# nano_control_station.net
KiCad netlist of a schematic drawn in EAGLE
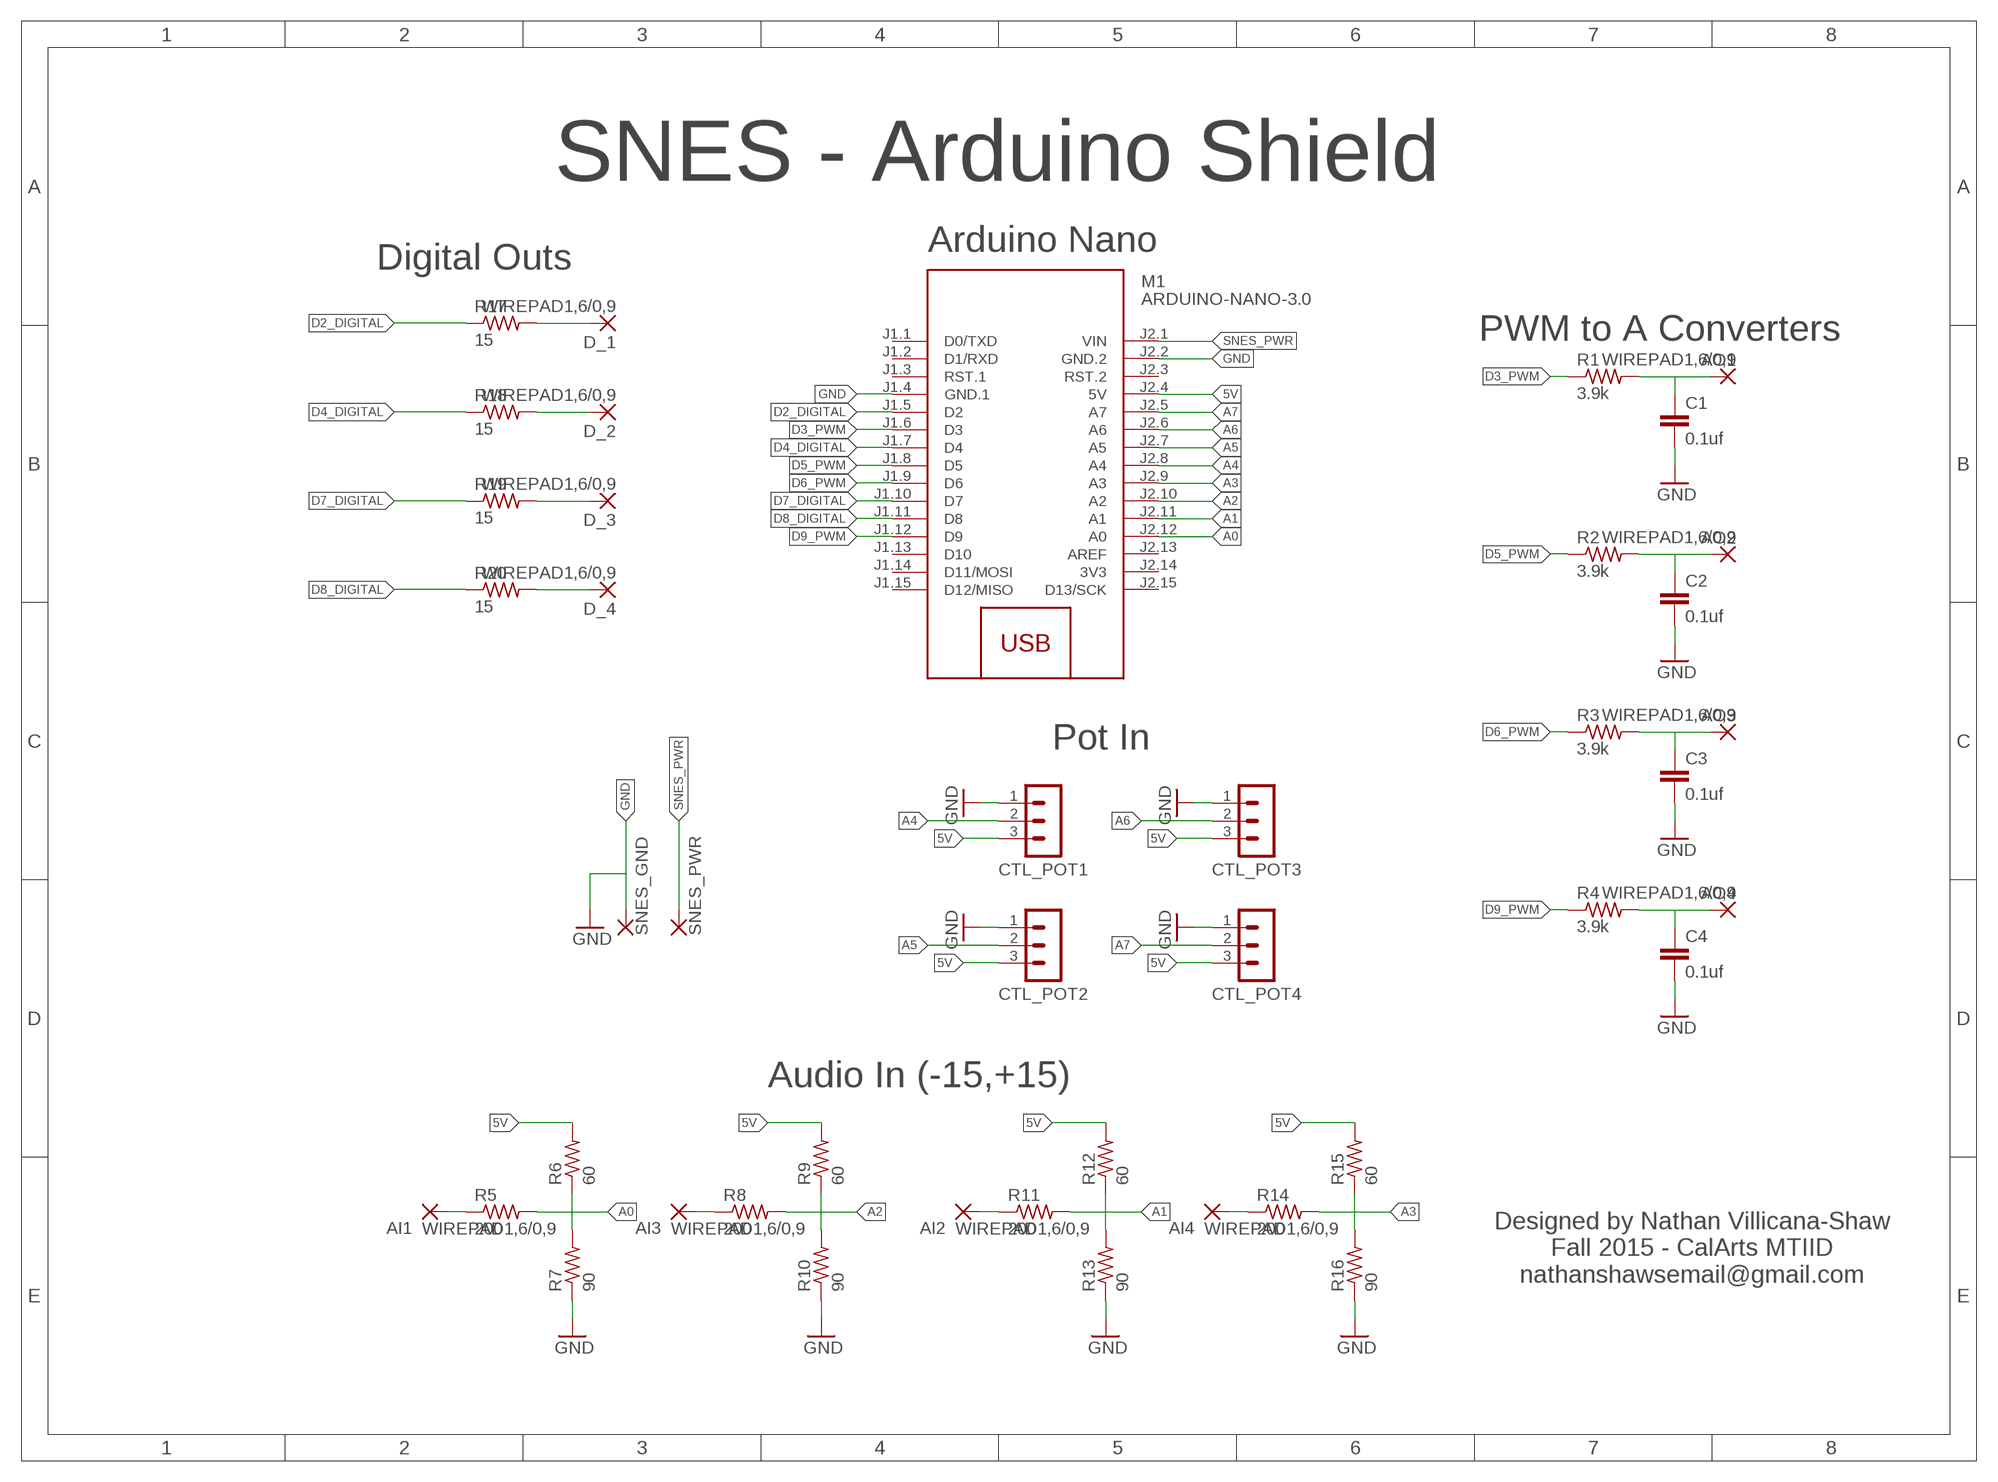
[diagram p0: schematic, sheet 1]

(export (version "E")
  (design (tool "Eeschema 10.0.6"))
  (components
    (comp (ref "AI1")
      (value "WIREPAD1,6/0,9")
      (footprint "eagle-import:1,6_0,9")
      (libsource (lib "eagle-import") (part "WIREPAD1,6/0,9"))
    )
    (comp (ref "AI2")
      (value "WIREPAD1,6/0,9")
      (footprint "eagle-import:1,6_0,9")
      (libsource (lib "eagle-import") (part "WIREPAD1,6/0,9"))
    )
    (comp (ref "AI3")
      (value "WIREPAD1,6/0,9")
      (footprint "eagle-import:1,6_0,9")
      (libsource (lib "eagle-import") (part "WIREPAD1,6/0,9"))
    )
    (comp (ref "AI4")
      (value "WIREPAD1,6/0,9")
      (footprint "eagle-import:1,6_0,9")
      (libsource (lib "eagle-import") (part "WIREPAD1,6/0,9"))
    )
    (comp (ref "AO1")
      (value "WIREPAD1,6/0,9")
      (footprint "eagle-import:1,6_0,9")
      (libsource (lib "eagle-import") (part "WIREPAD1,6/0,9"))
    )
    (comp (ref "AO2")
      (value "WIREPAD1,6/0,9")
      (footprint "eagle-import:1,6_0,9")
      (libsource (lib "eagle-import") (part "WIREPAD1,6/0,9"))
    )
    (comp (ref "AO3")
      (value "WIREPAD1,6/0,9")
      (footprint "eagle-import:1,6_0,9")
      (libsource (lib "eagle-import") (part "WIREPAD1,6/0,9"))
    )
    (comp (ref "AO4")
      (value "WIREPAD1,6/0,9")
      (footprint "eagle-import:1,6_0,9")
      (libsource (lib "eagle-import") (part "WIREPAD1,6/0,9"))
    )
    (comp (ref "C1")
      (value "0.1uf")
      (footprint "eagle-import:C2.5-2")
      (libsource (lib "eagle-import") (part "C2.5/2"))
    )
    (comp (ref "C2")
      (value "0.1uf")
      (footprint "eagle-import:C2.5-2")
      (libsource (lib "eagle-import") (part "C2.5/2"))
    )
    (comp (ref "C3")
      (value "0.1uf")
      (footprint "eagle-import:C2.5-2")
      (libsource (lib "eagle-import") (part "C2.5/2"))
    )
    (comp (ref "C4")
      (value "0.1uf")
      (footprint "eagle-import:C2.5-2")
      (libsource (lib "eagle-import") (part "C2.5/2"))
    )
    (comp (ref "CTL_POT1")
      (value "MA03-1")
      (footprint "eagle-import:MA03-1")
      (libsource (lib "eagle-import") (part "MA03-1"))
    )
    (comp (ref "CTL_POT2")
      (value "MA03-1")
      (footprint "eagle-import:MA03-1")
      (libsource (lib "eagle-import") (part "MA03-1"))
    )
    (comp (ref "CTL_POT3")
      (value "MA03-1")
      (footprint "eagle-import:MA03-1")
      (libsource (lib "eagle-import") (part "MA03-1"))
    )
    (comp (ref "CTL_POT4")
      (value "MA03-1")
      (footprint "eagle-import:MA03-1")
      (libsource (lib "eagle-import") (part "MA03-1"))
    )
    (comp (ref "D_1")
      (value "WIREPAD1,6/0,9")
      (footprint "eagle-import:1,6_0,9")
      (libsource (lib "eagle-import") (part "WIREPAD1,6/0,9"))
    )
    (comp (ref "D_2")
      (value "WIREPAD1,6/0,9")
      (footprint "eagle-import:1,6_0,9")
      (libsource (lib "eagle-import") (part "WIREPAD1,6/0,9"))
    )
    (comp (ref "D_3")
      (value "WIREPAD1,6/0,9")
      (footprint "eagle-import:1,6_0,9")
      (libsource (lib "eagle-import") (part "WIREPAD1,6/0,9"))
    )
    (comp (ref "D_4")
      (value "WIREPAD1,6/0,9")
      (footprint "eagle-import:1,6_0,9")
      (libsource (lib "eagle-import") (part "WIREPAD1,6/0,9"))
    )
    (comp (ref "M1")
      (value "ARDUINO-NANO-3.0")
      (footprint "eagle-import:ARDUINO-NANO-3.0")
      (libsource (lib "eagle-import") (part "ARDUINO-NANO-3.0"))
    )
    (comp (ref "R1")
      (value "3.9k")
      (footprint "eagle-import:0204_7")
      (libsource (lib "eagle-import") (part "R-US_0204/7"))
    )
    (comp (ref "R2")
      (value "3.9k")
      (footprint "eagle-import:0204_7")
      (libsource (lib "eagle-import") (part "R-US_0204/7"))
    )
    (comp (ref "R3")
      (value "3.9k")
      (footprint "eagle-import:0204_7")
      (libsource (lib "eagle-import") (part "R-US_0204/7"))
    )
    (comp (ref "R4")
      (value "3.9k")
      (footprint "eagle-import:0204_7")
      (libsource (lib "eagle-import") (part "R-US_0204/7"))
    )
    (comp (ref "R5")
      (value "200")
      (footprint "eagle-import:0204_7")
      (libsource (lib "eagle-import") (part "R-US_0204/7"))
    )
    (comp (ref "R6")
      (value "60")
      (footprint "eagle-import:0204_7")
      (libsource (lib "eagle-import") (part "R-US_0204/7"))
    )
    (comp (ref "R7")
      (value "90")
      (footprint "eagle-import:0204_7")
      (libsource (lib "eagle-import") (part "R-US_0204/7"))
    )
    (comp (ref "R8")
      (value "200")
      (footprint "eagle-import:0204_7")
      (libsource (lib "eagle-import") (part "R-US_0204/7"))
    )
    (comp (ref "R9")
      (value "60")
      (footprint "eagle-import:0204_7")
      (libsource (lib "eagle-import") (part "R-US_0204/7"))
    )
    (comp (ref "R10")
      (value "90")
      (footprint "eagle-import:0204_7")
      (libsource (lib "eagle-import") (part "R-US_0204/7"))
    )
    (comp (ref "R11")
      (value "200")
      (footprint "eagle-import:0204_7")
      (libsource (lib "eagle-import") (part "R-US_0204/7"))
    )
    (comp (ref "R12")
      (value "60")
      (footprint "eagle-import:0204_7")
      (libsource (lib "eagle-import") (part "R-US_0204/7"))
    )
    (comp (ref "R13")
      (value "90")
      (footprint "eagle-import:0204_7")
      (libsource (lib "eagle-import") (part "R-US_0204/7"))
    )
    (comp (ref "R14")
      (value "200")
      (footprint "eagle-import:0204_7")
      (libsource (lib "eagle-import") (part "R-US_0204/7"))
    )
    (comp (ref "R15")
      (value "60")
      (footprint "eagle-import:0204_7")
      (libsource (lib "eagle-import") (part "R-US_0204/7"))
    )
    (comp (ref "R16")
      (value "90")
      (footprint "eagle-import:0204_7")
      (libsource (lib "eagle-import") (part "R-US_0204/7"))
    )
    (comp (ref "R17")
      (value "15")
      (footprint "eagle-import:0204_7")
      (libsource (lib "eagle-import") (part "R-US_0204/7"))
    )
    (comp (ref "R18")
      (value "15")
      (footprint "eagle-import:0204_7")
      (libsource (lib "eagle-import") (part "R-US_0204/7"))
    )
    (comp (ref "R19")
      (value "15")
      (footprint "eagle-import:0204_7")
      (libsource (lib "eagle-import") (part "R-US_0204/7"))
    )
    (comp (ref "R20")
      (value "15")
      (footprint "eagle-import:0204_7")
      (libsource (lib "eagle-import") (part "R-US_0204/7"))
    )
    (comp (ref "SNES_GND")
      (value "2,15/1,0")
      (footprint "eagle-import:2,15_1,0")
      (libsource (lib "eagle-import") (part "2,15/1,0"))
    )
    (comp (ref "SNES_PWR")
      (value "2,15/1,0")
      (footprint "eagle-import:2,15_1,0")
      (libsource (lib "eagle-import") (part "2,15/1,0"))
    )
  )
  (nets
    (net (code "1") (name "/3V3") (class "Default")
      (node (ref "M1") (pin "J2.14") (pinfunction "3V3_J2.14") (pintype "power_in"))
    )
    (net (code "2") (name "5V") (class "Default")
      (node (ref "CTL_POT1") (pin "3") (pinfunction "3_3") (pintype "passive"))
      (node (ref "CTL_POT2") (pin "3") (pinfunction "3_3") (pintype "passive"))
      (node (ref "CTL_POT3") (pin "3") (pinfunction "3_3") (pintype "passive"))
      (node (ref "CTL_POT4") (pin "3") (pinfunction "3_3") (pintype "passive"))
      (node (ref "M1") (pin "J2.4") (pinfunction "5V_J2.4") (pintype "power_in"))
      (node (ref "R12") (pin "2") (pinfunction "2_2") (pintype "passive"))
      (node (ref "R15") (pin "2") (pinfunction "2_2") (pintype "passive"))
      (node (ref "R6") (pin "2") (pinfunction "2_2") (pintype "passive"))
      (node (ref "R9") (pin "2") (pinfunction "2_2") (pintype "passive"))
    )
    (net (code "3") (name "A0") (class "Default")
      (node (ref "M1") (pin "J2.12") (pinfunction "A0_J2.12") (pintype "bidirectional"))
      (node (ref "R5") (pin "2") (pinfunction "2_2") (pintype "passive"))
      (node (ref "R6") (pin "1") (pinfunction "1_1") (pintype "passive"))
      (node (ref "R7") (pin "2") (pinfunction "2_2") (pintype "passive"))
    )
    (net (code "4") (name "A1") (class "Default")
      (node (ref "M1") (pin "J2.11") (pinfunction "A1_J2.11") (pintype "bidirectional"))
      (node (ref "R11") (pin "2") (pinfunction "2_2") (pintype "passive"))
      (node (ref "R12") (pin "1") (pinfunction "1_1") (pintype "passive"))
      (node (ref "R13") (pin "2") (pinfunction "2_2") (pintype "passive"))
    )
    (net (code "5") (name "A2") (class "Default")
      (node (ref "M1") (pin "J2.10") (pinfunction "A2_J2.10") (pintype "bidirectional"))
      (node (ref "R10") (pin "2") (pinfunction "2_2") (pintype "passive"))
      (node (ref "R8") (pin "2") (pinfunction "2_2") (pintype "passive"))
      (node (ref "R9") (pin "1") (pinfunction "1_1") (pintype "passive"))
    )
    (net (code "6") (name "A3") (class "Default")
      (node (ref "M1") (pin "J2.9") (pinfunction "A3_J2.9") (pintype "bidirectional"))
      (node (ref "R14") (pin "2") (pinfunction "2_2") (pintype "passive"))
      (node (ref "R15") (pin "1") (pinfunction "1_1") (pintype "passive"))
      (node (ref "R16") (pin "2") (pinfunction "2_2") (pintype "passive"))
    )
    (net (code "7") (name "A4") (class "Default")
      (node (ref "CTL_POT1") (pin "2") (pinfunction "2_2") (pintype "passive"))
      (node (ref "M1") (pin "J2.8") (pinfunction "A4_J2.8") (pintype "bidirectional"))
    )
    (net (code "8") (name "A5") (class "Default")
      (node (ref "CTL_POT2") (pin "2") (pinfunction "2_2") (pintype "passive"))
      (node (ref "M1") (pin "J2.7") (pinfunction "A5_J2.7") (pintype "bidirectional"))
    )
    (net (code "9") (name "A6") (class "Default")
      (node (ref "CTL_POT3") (pin "2") (pinfunction "2_2") (pintype "passive"))
      (node (ref "M1") (pin "J2.6") (pinfunction "A6_J2.6") (pintype "bidirectional"))
    )
    (net (code "10") (name "A7") (class "Default")
      (node (ref "CTL_POT4") (pin "2") (pinfunction "2_2") (pintype "passive"))
      (node (ref "M1") (pin "J2.5") (pinfunction "A7_J2.5") (pintype "bidirectional"))
    )
    (net (code "11") (name "D2_DIGITAL") (class "Default")
      (node (ref "M1") (pin "J1.5") (pinfunction "D2_J1.5") (pintype "bidirectional"))
      (node (ref "R17") (pin "1") (pinfunction "1_1") (pintype "passive"))
    )
    (net (code "12") (name "D3_PWM") (class "Default")
      (node (ref "M1") (pin "J1.6") (pinfunction "D3_J1.6") (pintype "bidirectional"))
      (node (ref "R1") (pin "1") (pinfunction "1_1") (pintype "passive"))
    )
    (net (code "13") (name "D4_DIGITAL") (class "Default")
      (node (ref "M1") (pin "J1.7") (pinfunction "D4_J1.7") (pintype "bidirectional"))
      (node (ref "R18") (pin "1") (pinfunction "1_1") (pintype "passive"))
    )
    (net (code "14") (name "D5_PWM") (class "Default")
      (node (ref "M1") (pin "J1.8") (pinfunction "D5_J1.8") (pintype "bidirectional"))
      (node (ref "R2") (pin "1") (pinfunction "1_1") (pintype "passive"))
    )
    (net (code "15") (name "D6_PWM") (class "Default")
      (node (ref "M1") (pin "J1.9") (pinfunction "D6_J1.9") (pintype "bidirectional"))
      (node (ref "R3") (pin "1") (pinfunction "1_1") (pintype "passive"))
    )
    (net (code "16") (name "D7_DIGITAL") (class "Default")
      (node (ref "M1") (pin "J1.10") (pinfunction "D7_J1.10") (pintype "bidirectional"))
      (node (ref "R19") (pin "1") (pinfunction "1_1") (pintype "passive"))
    )
    (net (code "17") (name "D8_DIGITAL") (class "Default")
      (node (ref "M1") (pin "J1.11") (pinfunction "D8_J1.11") (pintype "bidirectional"))
      (node (ref "R20") (pin "1") (pinfunction "1_1") (pintype "passive"))
    )
    (net (code "18") (name "D9_PWM") (class "Default")
      (node (ref "M1") (pin "J1.12") (pinfunction "D9_J1.12") (pintype "bidirectional"))
      (node (ref "R4") (pin "1") (pinfunction "1_1") (pintype "passive"))
    )
    (net (code "19") (name "GND") (class "Default")
      (node (ref "C1") (pin "2") (pinfunction "2_2") (pintype "passive"))
      (node (ref "C2") (pin "2") (pinfunction "2_2") (pintype "passive"))
      (node (ref "C3") (pin "2") (pinfunction "2_2") (pintype "passive"))
      (node (ref "C4") (pin "2") (pinfunction "2_2") (pintype "passive"))
      (node (ref "CTL_POT1") (pin "1") (pinfunction "1_1") (pintype "passive"))
      (node (ref "CTL_POT2") (pin "1") (pinfunction "1_1") (pintype "passive"))
      (node (ref "CTL_POT3") (pin "1") (pinfunction "1_1") (pintype "passive"))
      (node (ref "CTL_POT4") (pin "1") (pinfunction "1_1") (pintype "passive"))
      (node (ref "M1") (pin "J1.4") (pinfunction "GND.1_J1.4") (pintype "power_in"))
      (node (ref "M1") (pin "J2.2") (pinfunction "GND.2_J2.2") (pintype "power_in"))
      (node (ref "R10") (pin "1") (pinfunction "1_1") (pintype "passive"))
      (node (ref "R13") (pin "1") (pinfunction "1_1") (pintype "passive"))
      (node (ref "R16") (pin "1") (pinfunction "1_1") (pintype "passive"))
      (node (ref "R7") (pin "1") (pinfunction "1_1") (pintype "passive"))
      (node (ref "SNES_GND") (pin "1") (pinfunction "P_1") (pintype "passive"))
    )
    (net (code "20") (name "Net-(AI1-P)") (class "Default")
      (node (ref "AI1") (pin "1") (pinfunction "P_1") (pintype "passive"))
      (node (ref "R5") (pin "1") (pinfunction "1_1") (pintype "passive"))
    )
    (net (code "21") (name "Net-(AI2-P)") (class "Default")
      (node (ref "AI2") (pin "1") (pinfunction "P_1") (pintype "passive"))
      (node (ref "R11") (pin "1") (pinfunction "1_1") (pintype "passive"))
    )
    (net (code "22") (name "Net-(AI3-P)") (class "Default")
      (node (ref "AI3") (pin "1") (pinfunction "P_1") (pintype "passive"))
      (node (ref "R8") (pin "1") (pinfunction "1_1") (pintype "passive"))
    )
    (net (code "23") (name "Net-(AI4-P)") (class "Default")
      (node (ref "AI4") (pin "1") (pinfunction "P_1") (pintype "passive"))
      (node (ref "R14") (pin "1") (pinfunction "1_1") (pintype "passive"))
    )
    (net (code "24") (name "Net-(AO1-P)") (class "Default")
      (node (ref "AO1") (pin "1") (pinfunction "P_1") (pintype "passive"))
      (node (ref "C1") (pin "1") (pinfunction "1_1") (pintype "passive"))
      (node (ref "R1") (pin "2") (pinfunction "2_2") (pintype "passive"))
    )
    (net (code "25") (name "Net-(AO2-P)") (class "Default")
      (node (ref "AO2") (pin "1") (pinfunction "P_1") (pintype "passive"))
      (node (ref "C2") (pin "1") (pinfunction "1_1") (pintype "passive"))
      (node (ref "R2") (pin "2") (pinfunction "2_2") (pintype "passive"))
    )
    (net (code "26") (name "Net-(AO3-P)") (class "Default")
      (node (ref "AO3") (pin "1") (pinfunction "P_1") (pintype "passive"))
      (node (ref "C3") (pin "1") (pinfunction "1_1") (pintype "passive"))
      (node (ref "R3") (pin "2") (pinfunction "2_2") (pintype "passive"))
    )
    (net (code "27") (name "Net-(AO4-P)") (class "Default")
      (node (ref "AO4") (pin "1") (pinfunction "P_1") (pintype "passive"))
      (node (ref "C4") (pin "1") (pinfunction "1_1") (pintype "passive"))
      (node (ref "R4") (pin "2") (pinfunction "2_2") (pintype "passive"))
    )
    (net (code "28") (name "Net-(D_1-P)") (class "Default")
      (node (ref "D_1") (pin "1") (pinfunction "P_1") (pintype "passive"))
      (node (ref "R17") (pin "2") (pinfunction "2_2") (pintype "passive"))
    )
    (net (code "29") (name "Net-(D_2-P)") (class "Default")
      (node (ref "D_2") (pin "1") (pinfunction "P_1") (pintype "passive"))
      (node (ref "R18") (pin "2") (pinfunction "2_2") (pintype "passive"))
    )
    (net (code "30") (name "Net-(D_3-P)") (class "Default")
      (node (ref "D_3") (pin "1") (pinfunction "P_1") (pintype "passive"))
      (node (ref "R19") (pin "2") (pinfunction "2_2") (pintype "passive"))
    )
    (net (code "31") (name "Net-(D_4-P)") (class "Default")
      (node (ref "D_4") (pin "1") (pinfunction "P_1") (pintype "passive"))
      (node (ref "R20") (pin "2") (pinfunction "2_2") (pintype "passive"))
    )
    (net (code "32") (name "SNES_PWR") (class "Default")
      (node (ref "M1") (pin "J2.1") (pinfunction "VIN_J2.1") (pintype "power_in"))
      (node (ref "SNES_PWR") (pin "1") (pinfunction "P_1") (pintype "passive"))
    )
    (net (code "33") (name "unconnected-(M1-AREF-PadJ2.13)") (class "Default")
      (node (ref "M1") (pin "J2.13") (pinfunction "AREF_J2.13") (pintype "bidirectional"))
    )
    (net (code "34") (name "unconnected-(M1-D0{slash}TXD-PadJ1.1)") (class "Default")
      (node (ref "M1") (pin "J1.1") (pinfunction "D0/TXD_J1.1") (pintype "bidirectional"))
    )
    (net (code "35") (name "unconnected-(M1-D1{slash}RXD-PadJ1.2)") (class "Default")
      (node (ref "M1") (pin "J1.2") (pinfunction "D1/RXD_J1.2") (pintype "bidirectional"))
    )
    (net (code "36") (name "unconnected-(M1-D10-PadJ1.13)") (class "Default")
      (node (ref "M1") (pin "J1.13") (pinfunction "D10_J1.13") (pintype "bidirectional"))
    )
    (net (code "37") (name "unconnected-(M1-D11{slash}MOSI-PadJ1.14)") (class "Default")
      (node (ref "M1") (pin "J1.14") (pinfunction "D11/MOSI_J1.14") (pintype "bidirectional"))
    )
    (net (code "38") (name "unconnected-(M1-D12{slash}MISO-PadJ1.15)") (class "Default")
      (node (ref "M1") (pin "J1.15") (pinfunction "D12/MISO_J1.15") (pintype "bidirectional"))
    )
    (net (code "39") (name "unconnected-(M1-D13{slash}SCK-PadJ2.15)") (class "Default")
      (node (ref "M1") (pin "J2.15") (pinfunction "D13/SCK_J2.15") (pintype "bidirectional"))
    )
    (net (code "40") (name "unconnected-(M1-RST.1-PadJ1.3)") (class "Default")
      (node (ref "M1") (pin "J1.3") (pinfunction "RST.1_J1.3") (pintype "bidirectional"))
    )
    (net (code "41") (name "unconnected-(M1-RST.2-PadJ2.3)") (class "Default")
      (node (ref "M1") (pin "J2.3") (pinfunction "RST.2_J2.3") (pintype "bidirectional"))
    )
  )
)
